# ESP8266.net
KiCad netlist of a schematic drawn in Altium Designer
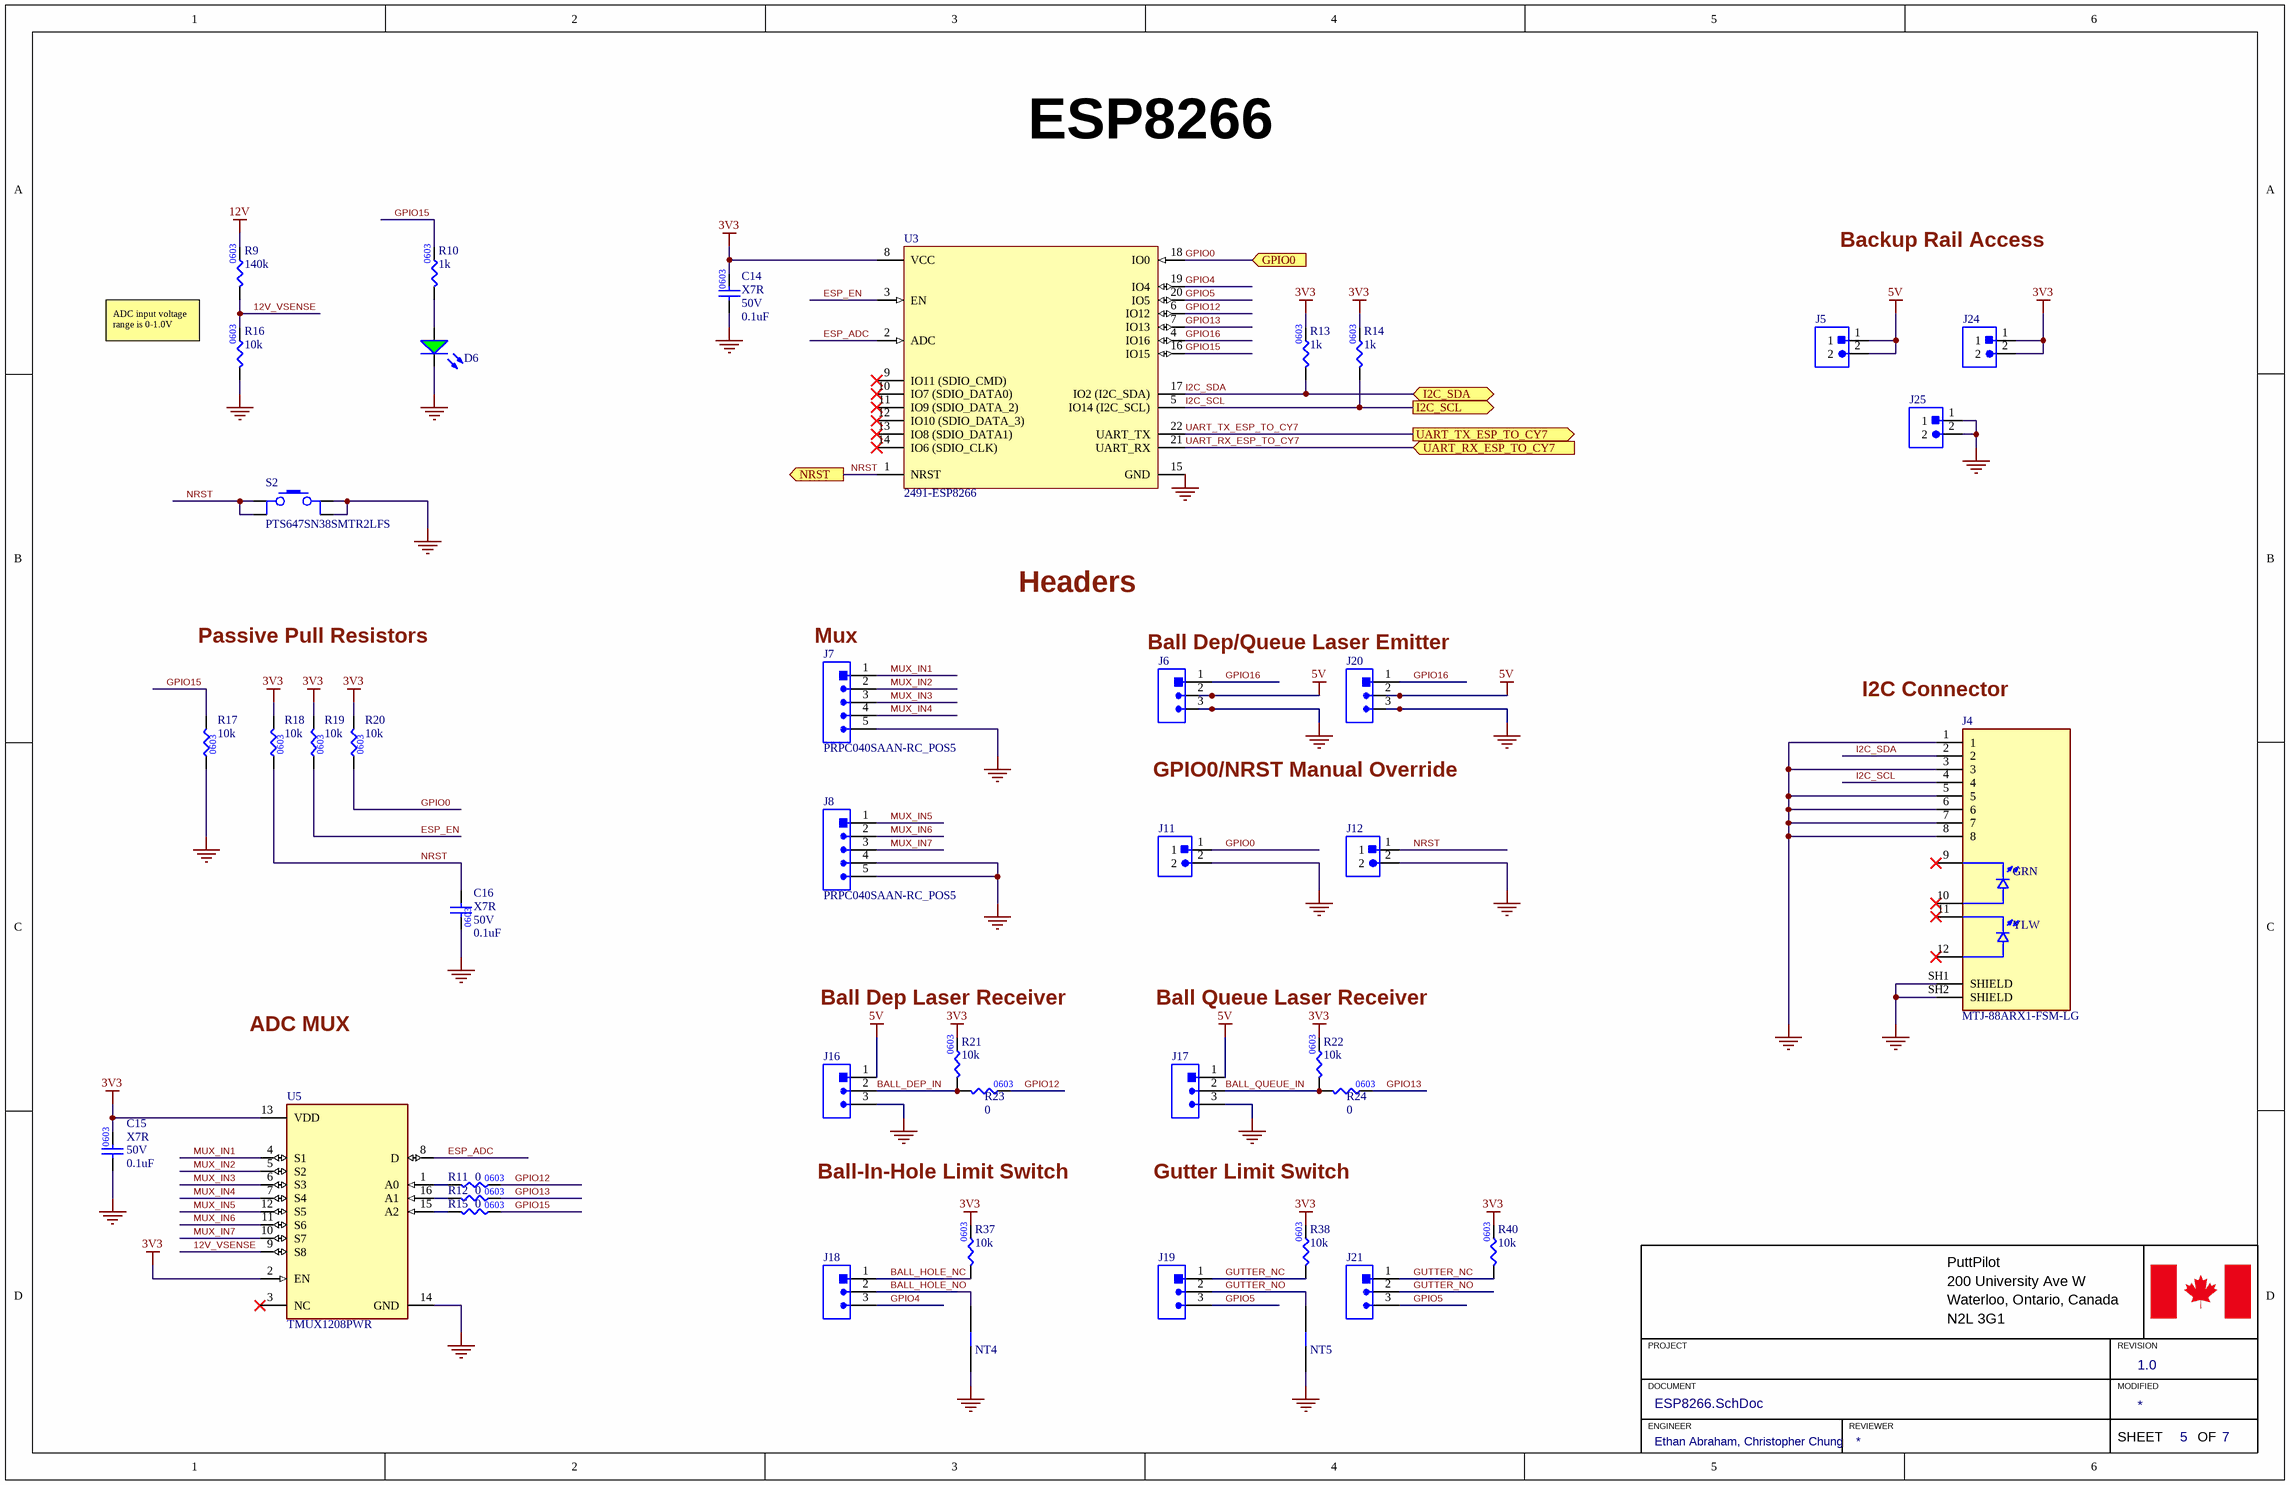
[diagram p0: ESP8266.SchDoc]

(export (version "E")
  (design (tool "Eeschema 10.0.6"))
  (components
    (comp (ref "C14")
      (value "GCJ188R71H104KA12D")
      (footprint ".CAP_0603")
      (description "CAP CER 0.1uF 50V X7R 0603")
      (fields
        (field (name "MANUFACTURER") "Murata")
        (field (name "TEMPERATURE CHARACTERISTICS CODE") "X7R")
        (field (name "RATED DC VOLTAGE (URDC)") "50V")
        (field (name "CAPACITANCE") "0.1uF")
      )
      (libsource (lib "PuttPilot") (part "GCJ188R71H104KA12D"))
    )
    (comp (ref "C15")
      (value "GCJ188R71H104KA12D")
      (footprint ".CAP_0603")
      (description "CAP CER 0.1uF 50V X7R 0603")
      (fields
        (field (name "MANUFACTURER") "Murata")
        (field (name "TEMPERATURE CHARACTERISTICS CODE") "X7R")
        (field (name "RATED DC VOLTAGE (URDC)") "50V")
        (field (name "CAPACITANCE") "0.1uF")
      )
      (libsource (lib "PuttPilot") (part "GCJ188R71H104KA12D"))
    )
    (comp (ref "C16")
      (value "GCJ188R71H104KA12D")
      (footprint ".CAP_0603")
      (description "CAP CER 0.1uF 50V X7R 0603")
      (fields
        (field (name "MANUFACTURER") "Murata")
        (field (name "TEMPERATURE CHARACTERISTICS CODE") "X7R")
        (field (name "RATED DC VOLTAGE (URDC)") "50V")
        (field (name "CAPACITANCE") "0.1uF")
      )
      (libsource (lib "PuttPilot") (part "GCJ188R71H104KA12D"))
    )
    (comp (ref "D6")
      (value "LTST-C191KGKT")
      (footprint ".LED_0603")
      (description "LED GREEN 2V 0603")
      (fields (field (name "MANUFACTURER") "Vishay Lite-On"))
      (libsource (lib "PuttPilot") (part "LTST-C191KGKT"))
    )
    (comp (ref "J4")
      (value "MTJ-88ARX1-FSM-LG")
      (footprint "MTJ-88ARX1-FSM-LG")
      (description "RJ45 JACK R/A SHIELDED")
      (fields (field (name "MANUFACTURER") "Adam Equipment"))
      (libsource (lib "PuttPilot") (part "MTJ-88ARX1-FSM-LG"))
    )
    (comp (ref "J5")
      (value "PRPC040SAAN-RC")
      (footprint "HEADER_2POS_2.54MM")
      (description "CONN HEADER VERT 2POS 2.54MM")
      (fields (field (name "MANUFACTURER") "Sullins"))
      (libsource (lib "PuttPilot") (part "PRPC040SAAN-RC_POS2"))
    )
    (comp (ref "J6")
      (value "PRPC040SAAN-RC")
      (footprint "HEADER_3POS_2.54MM")
      (description "CONN HEADER VERT 3POS 2.54MM")
      (fields (field (name "MANUFACTURER") "Sullins"))
      (libsource (lib "PuttPilot") (part "PRPC040SAAN-RC"))
    )
    (comp (ref "J7")
      (value "PRPC040SAAN-RC_POS5")
      (footprint "HEADER_5POS_2.54MM")
      (description "CONN HEADER VERT 5POS 2.54MM")
      (libsource (lib "PuttPilot") (part "PRPC040SAAN-RC_POS5"))
    )
    (comp (ref "J8")
      (value "PRPC040SAAN-RC_POS5")
      (footprint "HEADER_5POS_2.54MM")
      (description "CONN HEADER VERT 5POS 2.54MM")
      (libsource (lib "PuttPilot") (part "PRPC040SAAN-RC_POS5"))
    )
    (comp (ref "J11")
      (value "PRPC040SAAN-RC")
      (footprint "HEADER_2POS_2.54MM")
      (description "CONN HEADER VERT 2POS 2.54MM")
      (fields (field (name "MANUFACTURER") "Sullins"))
      (libsource (lib "PuttPilot") (part "PRPC040SAAN-RC_POS2"))
    )
    (comp (ref "J12")
      (value "PRPC040SAAN-RC")
      (footprint "HEADER_2POS_2.54MM")
      (description "CONN HEADER VERT 2POS 2.54MM")
      (fields (field (name "MANUFACTURER") "Sullins"))
      (libsource (lib "PuttPilot") (part "PRPC040SAAN-RC_POS2"))
    )
    (comp (ref "J16")
      (value "PRPC040SAAN-RC")
      (footprint "HEADER_3POS_2.54MM")
      (description "CONN HEADER VERT 3POS 2.54MM")
      (fields (field (name "MANUFACTURER") "Sullins"))
      (libsource (lib "PuttPilot") (part "PRPC040SAAN-RC"))
    )
    (comp (ref "J17")
      (value "PRPC040SAAN-RC")
      (footprint "HEADER_3POS_2.54MM")
      (description "CONN HEADER VERT 3POS 2.54MM")
      (fields (field (name "MANUFACTURER") "Sullins"))
      (libsource (lib "PuttPilot") (part "PRPC040SAAN-RC"))
    )
    (comp (ref "J18")
      (value "PRPC040SAAN-RC")
      (footprint "HEADER_3POS_2.54MM")
      (description "CONN HEADER VERT 3POS 2.54MM")
      (fields (field (name "MANUFACTURER") "Sullins"))
      (libsource (lib "PuttPilot") (part "PRPC040SAAN-RC"))
    )
    (comp (ref "J19")
      (value "PRPC040SAAN-RC")
      (footprint "HEADER_3POS_2.54MM")
      (description "CONN HEADER VERT 3POS 2.54MM")
      (fields (field (name "MANUFACTURER") "Sullins"))
      (libsource (lib "PuttPilot") (part "PRPC040SAAN-RC"))
    )
    (comp (ref "J20")
      (value "PRPC040SAAN-RC")
      (footprint "HEADER_3POS_2.54MM")
      (description "CONN HEADER VERT 3POS 2.54MM")
      (fields (field (name "MANUFACTURER") "Sullins"))
      (libsource (lib "PuttPilot") (part "PRPC040SAAN-RC"))
    )
    (comp (ref "J21")
      (value "PRPC040SAAN-RC")
      (footprint "HEADER_3POS_2.54MM")
      (description "CONN HEADER VERT 3POS 2.54MM")
      (fields (field (name "MANUFACTURER") "Sullins"))
      (libsource (lib "PuttPilot") (part "PRPC040SAAN-RC"))
    )
    (comp (ref "J24")
      (value "PRPC040SAAN-RC")
      (footprint "HEADER_2POS_2.54MM")
      (description "CONN HEADER VERT 2POS 2.54MM")
      (fields (field (name "MANUFACTURER") "Sullins"))
      (libsource (lib "PuttPilot") (part "PRPC040SAAN-RC_POS2"))
    )
    (comp (ref "J25")
      (value "PRPC040SAAN-RC")
      (footprint "HEADER_2POS_2.54MM")
      (description "CONN HEADER VERT 2POS 2.54MM")
      (fields (field (name "MANUFACTURER") "Sullins"))
      (libsource (lib "PuttPilot") (part "PRPC040SAAN-RC_POS2"))
    )
    (comp (ref "NT4")
      (value ".NET_TIE")
      (footprint ".NET_TIE")
      (description ".GENERIC NET TIE")
      (libsource (lib "PuttPilot") (part ".NET_TIE"))
    )
    (comp (ref "NT5")
      (value ".NET_TIE")
      (footprint ".NET_TIE")
      (description ".GENERIC NET TIE")
      (libsource (lib "PuttPilot") (part ".NET_TIE"))
    )
    (comp (ref "R9")
      (value "RC0603FR-07140KL")
      (footprint ".RES_0603")
      (description "RES 140K OHM 0603")
      (fields
        (field (name "MANUFACTURER") "Yageo")
        (field (name "TOLERANCE") "1%")
        (field (name "RESISTANCE") "140k")
      )
      (libsource (lib "PuttPilot") (part "RC0603FR-07140KL"))
    )
    (comp (ref "R10")
      (value "RC0603FR-071KL")
      (footprint ".RES_0603")
      (description "RES 1K OHM 0603")
      (fields
        (field (name "MANUFACTURER") "Yageo")
        (field (name "TOLERANCE") "1%")
        (field (name "RESISTANCE") "1k")
      )
      (libsource (lib "PuttPilot") (part "RC0603FR-071KL"))
    )
    (comp (ref "R11")
      (value "RC0603JR-070RL")
      (footprint ".RES_0603")
      (description "RES 0 OHM 0603")
      (fields
        (field (name "MANUFACTURER") "Yageo")
        (field (name "MANUFACTURER PART NUMBER") "RC0603FR-071KL")
        (field (name "RESISTANCE") "0")
      )
      (libsource (lib "PuttPilot") (part "RC0603JR-070RL"))
    )
    (comp (ref "R12")
      (value "RC0603JR-070RL")
      (footprint ".RES_0603")
      (description "RES 0 OHM 0603")
      (fields
        (field (name "MANUFACTURER") "Yageo")
        (field (name "MANUFACTURER PART NUMBER") "RC0603FR-071KL")
        (field (name "RESISTANCE") "0")
      )
      (libsource (lib "PuttPilot") (part "RC0603JR-070RL"))
    )
    (comp (ref "R13")
      (value "RC0603FR-071KL")
      (footprint ".RES_0603")
      (description "RES 1K OHM 0603")
      (fields
        (field (name "MANUFACTURER") "Yageo")
        (field (name "TOLERANCE") "1%")
        (field (name "RESISTANCE") "1k")
      )
      (libsource (lib "PuttPilot") (part "RC0603FR-071KL"))
    )
    (comp (ref "R14")
      (value "RC0603FR-071KL")
      (footprint ".RES_0603")
      (description "RES 1K OHM 0603")
      (fields
        (field (name "MANUFACTURER") "Yageo")
        (field (name "TOLERANCE") "1%")
        (field (name "RESISTANCE") "1k")
      )
      (libsource (lib "PuttPilot") (part "RC0603FR-071KL"))
    )
    (comp (ref "R15")
      (value "RC0603JR-070RL")
      (footprint ".RES_0603")
      (description "RES 0 OHM 0603")
      (fields
        (field (name "MANUFACTURER") "Yageo")
        (field (name "MANUFACTURER PART NUMBER") "RC0603FR-071KL")
        (field (name "RESISTANCE") "0")
      )
      (libsource (lib "PuttPilot") (part "RC0603JR-070RL"))
    )
    (comp (ref "R16")
      (value "RC0603FR-0710KL")
      (footprint ".RES_0603")
      (description "RES 10K OHM 0603")
      (fields
        (field (name "MANUFACTURER") "Yageo")
        (field (name "TOLERANCE") "1%")
        (field (name "RESISTANCE") "10k")
      )
      (libsource (lib "PuttPilot") (part "RC0603FR-0710KL"))
    )
    (comp (ref "R17")
      (value "RC0603FR-0710KL")
      (footprint ".RES_0603")
      (description "RES 10K OHM 0603")
      (fields
        (field (name "MANUFACTURER") "Yageo")
        (field (name "TOLERANCE") "1%")
        (field (name "RESISTANCE") "10k")
      )
      (libsource (lib "PuttPilot") (part "RC0603FR-0710KL"))
    )
    (comp (ref "R18")
      (value "RC0603FR-0710KL")
      (footprint ".RES_0603")
      (description "RES 10K OHM 0603")
      (fields
        (field (name "MANUFACTURER") "Yageo")
        (field (name "TOLERANCE") "1%")
        (field (name "RESISTANCE") "10k")
      )
      (libsource (lib "PuttPilot") (part "RC0603FR-0710KL"))
    )
    (comp (ref "R19")
      (value "RC0603FR-0710KL")
      (footprint ".RES_0603")
      (description "RES 10K OHM 0603")
      (fields
        (field (name "MANUFACTURER") "Yageo")
        (field (name "TOLERANCE") "1%")
        (field (name "RESISTANCE") "10k")
      )
      (libsource (lib "PuttPilot") (part "RC0603FR-0710KL"))
    )
    (comp (ref "R20")
      (value "RC0603FR-0710KL")
      (footprint ".RES_0603")
      (description "RES 10K OHM 0603")
      (fields
        (field (name "MANUFACTURER") "Yageo")
        (field (name "TOLERANCE") "1%")
        (field (name "RESISTANCE") "10k")
      )
      (libsource (lib "PuttPilot") (part "RC0603FR-0710KL"))
    )
    (comp (ref "R21")
      (value "RC0603FR-0710KL")
      (footprint ".RES_0603")
      (description "RES 10K OHM 0603")
      (fields
        (field (name "MANUFACTURER") "Yageo")
        (field (name "TOLERANCE") "1%")
        (field (name "RESISTANCE") "10k")
      )
      (libsource (lib "PuttPilot") (part "RC0603FR-0710KL"))
    )
    (comp (ref "R22")
      (value "RC0603FR-0710KL")
      (footprint ".RES_0603")
      (description "RES 10K OHM 0603")
      (fields
        (field (name "MANUFACTURER") "Yageo")
        (field (name "TOLERANCE") "1%")
        (field (name "RESISTANCE") "10k")
      )
      (libsource (lib "PuttPilot") (part "RC0603FR-0710KL"))
    )
    (comp (ref "R23")
      (value "RC0603JR-070RL")
      (footprint ".RES_0603")
      (description "RES 0 OHM 0603")
      (fields
        (field (name "MANUFACTURER") "Yageo")
        (field (name "MANUFACTURER PART NUMBER") "RC0603FR-071KL")
        (field (name "RESISTANCE") "0")
      )
      (libsource (lib "PuttPilot") (part "RC0603JR-070RL"))
    )
    (comp (ref "R24")
      (value "RC0603JR-070RL")
      (footprint ".RES_0603")
      (description "RES 0 OHM 0603")
      (fields
        (field (name "MANUFACTURER") "Yageo")
        (field (name "MANUFACTURER PART NUMBER") "RC0603FR-071KL")
        (field (name "RESISTANCE") "0")
      )
      (libsource (lib "PuttPilot") (part "RC0603JR-070RL"))
    )
    (comp (ref "R37")
      (value "RC0603FR-0710KL")
      (footprint ".RES_0603")
      (description "RES 10K OHM 0603")
      (fields
        (field (name "MANUFACTURER") "Yageo")
        (field (name "TOLERANCE") "1%")
        (field (name "RESISTANCE") "10k")
      )
      (libsource (lib "PuttPilot") (part "RC0603FR-0710KL"))
    )
    (comp (ref "R38")
      (value "RC0603FR-0710KL")
      (footprint ".RES_0603")
      (description "RES 10K OHM 0603")
      (fields
        (field (name "MANUFACTURER") "Yageo")
        (field (name "TOLERANCE") "1%")
        (field (name "RESISTANCE") "10k")
      )
      (libsource (lib "PuttPilot") (part "RC0603FR-0710KL"))
    )
    (comp (ref "R40")
      (value "RC0603FR-0710KL")
      (footprint ".RES_0603")
      (description "RES 10K OHM 0603")
      (fields
        (field (name "MANUFACTURER") "Yageo")
        (field (name "TOLERANCE") "1%")
        (field (name "RESISTANCE") "10k")
      )
      (libsource (lib "PuttPilot") (part "RC0603FR-0710KL"))
    )
    (comp (ref "S2")
      (value "PTS647SN38SMTR2LFS")
      (footprint "PTS647SN38SMTR2LFS")
      (description "SWITCH TACTILE SPST-NO 0.05A 12V")
      (fields (field (name "MANUFACTURER") "ITT C&K"))
      (libsource (lib "PuttPilot") (part "PTS647SN38SMTR2LFS"))
    )
    (comp (ref "U3")
      (value "2491-ESP8266")
      (footprint "2491-ESP8266")
      (description "ESP8266 + Trace Antenna, 4MB Flash")
      (libsource (lib "PuttPilot") (part "2491-ESP8266"))
    )
    (comp (ref "U5")
      (value "TMUX1208PWR")
      (footprint "TMUX1208")
      (description "Single-Ended Multiplexer, 1 Func, 8 Channel, CMOS, PDSO16")
      (fields (field (name "MANUFACTURER") "Texas Instruments"))
      (libsource (lib "PuttPilot") (part "TMUX1208PWR"))
    )
  )
  (nets
    (net (code "1") (name "/12V_VSENSE") (class "Default")
      (node (ref "R16") (pin "2") (pinfunction "2_2") (pintype "passive"))
      (node (ref "R9") (pin "1") (pinfunction "1_1") (pintype "passive"))
      (node (ref "U5") (pin "9") (pinfunction "S8_9") (pintype "bidirectional"))
    )
    (net (code "2") (name "/BALL_DEP_IN") (class "Default")
      (node (ref "J16") (pin "2") (pinfunction "2_2") (pintype "passive"))
      (node (ref "R21") (pin "1") (pinfunction "1_1") (pintype "passive"))
      (node (ref "R23") (pin "1") (pinfunction "1_1") (pintype "passive"))
    )
    (net (code "3") (name "/BALL_HOLE_NC") (class "Default")
      (node (ref "J18") (pin "1") (pinfunction "1_1") (pintype "passive"))
      (node (ref "R37") (pin "1") (pinfunction "1_1") (pintype "passive"))
    )
    (net (code "4") (name "/BALL_HOLE_NO") (class "Default")
      (node (ref "J18") (pin "2") (pinfunction "2_2") (pintype "passive"))
      (node (ref "NT4") (pin "2") (pinfunction "2_2") (pintype "passive"))
    )
    (net (code "5") (name "/BALL_QUEUE_IN") (class "Default")
      (node (ref "J17") (pin "2") (pinfunction "2_2") (pintype "passive"))
      (node (ref "R22") (pin "1") (pinfunction "1_1") (pintype "passive"))
      (node (ref "R24") (pin "1") (pinfunction "1_1") (pintype "passive"))
    )
    (net (code "6") (name "/ESP_ADC") (class "Default")
      (node (ref "U3") (pin "2") (pinfunction "ADC_2") (pintype "input"))
      (node (ref "U5") (pin "8") (pinfunction "D_8") (pintype "bidirectional"))
    )
    (net (code "7") (name "/ESP_EN") (class "Default")
      (node (ref "R19") (pin "1") (pinfunction "1_1") (pintype "passive"))
      (node (ref "U3") (pin "3") (pinfunction "EN_3") (pintype "input"))
    )
    (net (code "8") (name "/GPIO0") (class "Default")
      (node (ref "J11") (pin "1") (pinfunction "1_1") (pintype "passive"))
      (node (ref "R20") (pin "1") (pinfunction "1_1") (pintype "passive"))
      (node (ref "U3") (pin "18") (pinfunction "IO0_18") (pintype "input"))
    )
    (net (code "9") (name "/GPIO4") (class "Default")
      (node (ref "J18") (pin "3") (pinfunction "3_3") (pintype "passive"))
      (node (ref "U3") (pin "19") (pinfunction "IO4_19") (pintype "bidirectional"))
    )
    (net (code "10") (name "/GPIO5") (class "Default")
      (node (ref "J19") (pin "3") (pinfunction "3_3") (pintype "passive"))
      (node (ref "J21") (pin "3") (pinfunction "3_3") (pintype "passive"))
      (node (ref "U3") (pin "20") (pinfunction "IO5_20") (pintype "bidirectional"))
    )
    (net (code "11") (name "/GPIO12") (class "Default")
      (node (ref "R11") (pin "2") (pinfunction "2_2") (pintype "passive"))
      (node (ref "R23") (pin "2") (pinfunction "2_2") (pintype "passive"))
      (node (ref "U3") (pin "6") (pinfunction "IO12_6") (pintype "bidirectional"))
    )
    (net (code "12") (name "/GPIO13") (class "Default")
      (node (ref "R12") (pin "2") (pinfunction "2_2") (pintype "passive"))
      (node (ref "R24") (pin "2") (pinfunction "2_2") (pintype "passive"))
      (node (ref "U3") (pin "7") (pinfunction "IO13_7") (pintype "bidirectional"))
    )
    (net (code "13") (name "/GPIO15") (class "Default")
      (node (ref "R10") (pin "2") (pinfunction "2_2") (pintype "passive"))
      (node (ref "R15") (pin "2") (pinfunction "2_2") (pintype "passive"))
      (node (ref "R17") (pin "2") (pinfunction "2_2") (pintype "passive"))
      (node (ref "U3") (pin "16") (pinfunction "IO15_16") (pintype "bidirectional"))
    )
    (net (code "14") (name "/GPIO16") (class "Default")
      (node (ref "J20") (pin "1") (pinfunction "1_1") (pintype "passive"))
      (node (ref "J6") (pin "1") (pinfunction "1_1") (pintype "passive"))
      (node (ref "U3") (pin "4") (pinfunction "IO16_4") (pintype "bidirectional"))
    )
    (net (code "15") (name "/GUTTER_NC") (class "Default")
      (node (ref "J19") (pin "1") (pinfunction "1_1") (pintype "passive"))
      (node (ref "J21") (pin "1") (pinfunction "1_1") (pintype "passive"))
      (node (ref "R38") (pin "1") (pinfunction "1_1") (pintype "passive"))
      (node (ref "R40") (pin "1") (pinfunction "1_1") (pintype "passive"))
    )
    (net (code "16") (name "/GUTTER_NO") (class "Default")
      (node (ref "J19") (pin "2") (pinfunction "2_2") (pintype "passive"))
      (node (ref "J21") (pin "2") (pinfunction "2_2") (pintype "passive"))
      (node (ref "NT5") (pin "2") (pinfunction "2_2") (pintype "passive"))
    )
    (net (code "17") (name "/I2C_SCL") (class "Default")
      (node (ref "J4") (pin "4") (pinfunction "4_4") (pintype "passive"))
      (node (ref "R14") (pin "1") (pinfunction "1_1") (pintype "passive"))
      (node (ref "U3") (pin "5") (pinfunction "IO14_(I2C_SCL)_5") (pintype "passive"))
    )
    (net (code "18") (name "/I2C_SDA") (class "Default")
      (node (ref "J4") (pin "2") (pinfunction "2_2") (pintype "passive"))
      (node (ref "R13") (pin "1") (pinfunction "1_1") (pintype "passive"))
      (node (ref "U3") (pin "17") (pinfunction "IO2_(I2C_SDA)_17") (pintype "passive"))
    )
    (net (code "19") (name "/MUX_IN1") (class "Default")
      (node (ref "J7") (pin "1") (pinfunction "1_1") (pintype "passive"))
      (node (ref "U5") (pin "4") (pinfunction "S1_4") (pintype "bidirectional"))
    )
    (net (code "20") (name "/MUX_IN2") (class "Default")
      (node (ref "J7") (pin "2") (pinfunction "2_2") (pintype "passive"))
      (node (ref "U5") (pin "5") (pinfunction "S2_5") (pintype "bidirectional"))
    )
    (net (code "21") (name "/MUX_IN3") (class "Default")
      (node (ref "J7") (pin "3") (pinfunction "3_3") (pintype "passive"))
      (node (ref "U5") (pin "6") (pinfunction "S3_6") (pintype "bidirectional"))
    )
    (net (code "22") (name "/MUX_IN4") (class "Default")
      (node (ref "J7") (pin "4") (pinfunction "4_4") (pintype "passive"))
      (node (ref "U5") (pin "7") (pinfunction "S4_7") (pintype "bidirectional"))
    )
    (net (code "23") (name "/MUX_IN5") (class "Default")
      (node (ref "J8") (pin "1") (pinfunction "1_1") (pintype "passive"))
      (node (ref "U5") (pin "12") (pinfunction "S5_12") (pintype "bidirectional"))
    )
    (net (code "24") (name "/MUX_IN6") (class "Default")
      (node (ref "J8") (pin "2") (pinfunction "2_2") (pintype "passive"))
      (node (ref "U5") (pin "11") (pinfunction "S6_11") (pintype "bidirectional"))
    )
    (net (code "25") (name "/MUX_IN7") (class "Default")
      (node (ref "J8") (pin "3") (pinfunction "3_3") (pintype "passive"))
      (node (ref "U5") (pin "10") (pinfunction "S7_10") (pintype "bidirectional"))
    )
    (net (code "26") (name "/NRST") (class "Default")
      (node (ref "C16") (pin "2") (pinfunction "2_2") (pintype "passive"))
      (node (ref "J12") (pin "1") (pinfunction "1_1") (pintype "passive"))
      (node (ref "R18") (pin "1") (pinfunction "1_1") (pintype "passive"))
      (node (ref "S2") (pin "1") (pinfunction "1_1") (pintype "passive"))
      (node (ref "S2") (pin "2") (pinfunction "2_2") (pintype "passive"))
      (node (ref "U3") (pin "1") (pinfunction "NRST_1") (pintype "passive"))
    )
    (net (code "27") (name "/UART_RX_ESP_TO_CY7") (class "Default")
      (node (ref "U3") (pin "21") (pinfunction "UART_RX_21") (pintype "passive"))
    )
    (net (code "28") (name "/UART_TX_ESP_TO_CY7") (class "Default")
      (node (ref "U3") (pin "22") (pinfunction "UART_TX_22") (pintype "passive"))
    )
    (net (code "29") (name "3V3") (class "Default")
      (node (ref "C14") (pin "2") (pinfunction "2_2") (pintype "passive"))
      (node (ref "C15") (pin "2") (pinfunction "2_2") (pintype "passive"))
      (node (ref "J24") (pin "1") (pinfunction "1_1") (pintype "passive"))
      (node (ref "J24") (pin "2") (pinfunction "2_2") (pintype "passive"))
      (node (ref "R13") (pin "2") (pinfunction "2_2") (pintype "passive"))
      (node (ref "R14") (pin "2") (pinfunction "2_2") (pintype "passive"))
      (node (ref "R18") (pin "2") (pinfunction "2_2") (pintype "passive"))
      (node (ref "R19") (pin "2") (pinfunction "2_2") (pintype "passive"))
      (node (ref "R20") (pin "2") (pinfunction "2_2") (pintype "passive"))
      (node (ref "R21") (pin "2") (pinfunction "2_2") (pintype "passive"))
      (node (ref "R22") (pin "2") (pinfunction "2_2") (pintype "passive"))
      (node (ref "R37") (pin "2") (pinfunction "2_2") (pintype "passive"))
      (node (ref "R38") (pin "2") (pinfunction "2_2") (pintype "passive"))
      (node (ref "R40") (pin "2") (pinfunction "2_2") (pintype "passive"))
      (node (ref "U3") (pin "8") (pinfunction "VCC_8") (pintype "power_in"))
      (node (ref "U5") (pin "13") (pinfunction "VDD_13") (pintype "power_in"))
      (node (ref "U5") (pin "2") (pinfunction "EN_2") (pintype "input"))
    )
    (net (code "30") (name "5V") (class "Default")
      (node (ref "J16") (pin "1") (pinfunction "1_1") (pintype "passive"))
      (node (ref "J17") (pin "1") (pinfunction "1_1") (pintype "passive"))
      (node (ref "J20") (pin "2") (pinfunction "2_2") (pintype "passive"))
      (node (ref "J5") (pin "1") (pinfunction "1_1") (pintype "passive"))
      (node (ref "J5") (pin "2") (pinfunction "2_2") (pintype "passive"))
      (node (ref "J6") (pin "2") (pinfunction "2_2") (pintype "passive"))
    )
    (net (code "31") (name "12V") (class "Default")
      (node (ref "R9") (pin "2") (pinfunction "2_2") (pintype "passive"))
    )
    (net (code "32") (name "GND") (class "Default")
      (node (ref "C14") (pin "1") (pinfunction "1_1") (pintype "passive"))
      (node (ref "C15") (pin "1") (pinfunction "1_1") (pintype "passive"))
      (node (ref "C16") (pin "1") (pinfunction "1_1") (pintype "passive"))
      (node (ref "D6") (pin "2") (pinfunction "K_2") (pintype "passive"))
      (node (ref "J11") (pin "2") (pinfunction "2_2") (pintype "passive"))
      (node (ref "J12") (pin "2") (pinfunction "2_2") (pintype "passive"))
      (node (ref "J16") (pin "3") (pinfunction "3_3") (pintype "passive"))
      (node (ref "J17") (pin "3") (pinfunction "3_3") (pintype "passive"))
      (node (ref "J20") (pin "3") (pinfunction "3_3") (pintype "passive"))
      (node (ref "J25") (pin "1") (pinfunction "1_1") (pintype "passive"))
      (node (ref "J25") (pin "2") (pinfunction "2_2") (pintype "passive"))
      (node (ref "J4") (pin "1") (pinfunction "1_1") (pintype "passive"))
      (node (ref "J4") (pin "3") (pinfunction "3_3") (pintype "passive"))
      (node (ref "J4") (pin "5") (pinfunction "5_5") (pintype "passive"))
      (node (ref "J4") (pin "6") (pinfunction "6_6") (pintype "passive"))
      (node (ref "J4") (pin "7") (pinfunction "7_7") (pintype "passive"))
      (node (ref "J4") (pin "8") (pinfunction "8_8") (pintype "passive"))
      (node (ref "J4") (pin "SH1") (pinfunction "SHIELD_SH1") (pintype "passive"))
      (node (ref "J4") (pin "SH2") (pinfunction "SHIELD_SH2") (pintype "passive"))
      (node (ref "J6") (pin "3") (pinfunction "3_3") (pintype "passive"))
      (node (ref "J7") (pin "5") (pinfunction "5_5") (pintype "passive"))
      (node (ref "J8") (pin "4") (pinfunction "4_4") (pintype "passive"))
      (node (ref "J8") (pin "5") (pinfunction "5_5") (pintype "passive"))
      (node (ref "NT4") (pin "1") (pinfunction "1_1") (pintype "passive"))
      (node (ref "NT5") (pin "1") (pinfunction "1_1") (pintype "passive"))
      (node (ref "R16") (pin "1") (pinfunction "1_1") (pintype "passive"))
      (node (ref "R17") (pin "1") (pinfunction "1_1") (pintype "passive"))
      (node (ref "S2") (pin "3") (pinfunction "3_3") (pintype "passive"))
      (node (ref "S2") (pin "4") (pinfunction "4_4") (pintype "passive"))
      (node (ref "U3") (pin "15") (pinfunction "GND_15") (pintype "power_in"))
      (node (ref "U5") (pin "14") (pinfunction "GND_14") (pintype "power_in"))
    )
    (net (code "33") (name "Net-(D6-A)") (class "Default")
      (node (ref "D6") (pin "1") (pinfunction "A_1") (pintype "passive"))
      (node (ref "R10") (pin "1") (pinfunction "1_1") (pintype "passive"))
    )
    (net (code "34") (name "Net-(U5-A0)") (class "Default")
      (node (ref "R11") (pin "1") (pinfunction "1_1") (pintype "passive"))
      (node (ref "U5") (pin "1") (pinfunction "A0_1") (pintype "input"))
    )
    (net (code "35") (name "Net-(U5-A1)") (class "Default")
      (node (ref "R12") (pin "1") (pinfunction "1_1") (pintype "passive"))
      (node (ref "U5") (pin "16") (pinfunction "A1_16") (pintype "input"))
    )
    (net (code "36") (name "Net-(U5-A2)") (class "Default")
      (node (ref "R15") (pin "1") (pinfunction "1_1") (pintype "passive"))
      (node (ref "U5") (pin "15") (pinfunction "A2_15") (pintype "input"))
    )
    (net (code "37") (name "unconnected-(J4-Pad9)") (class "Default")
      (node (ref "J4") (pin "9") (pinfunction "9_9") (pintype "passive+no_connect"))
    )
    (net (code "38") (name "unconnected-(J4-Pad10)") (class "Default")
      (node (ref "J4") (pin "10") (pinfunction "10_10") (pintype "passive+no_connect"))
    )
    (net (code "39") (name "unconnected-(J4-Pad11)") (class "Default")
      (node (ref "J4") (pin "11") (pinfunction "11_11") (pintype "passive+no_connect"))
    )
    (net (code "40") (name "unconnected-(J4-Pad12)") (class "Default")
      (node (ref "J4") (pin "12") (pinfunction "12_12") (pintype "passive+no_connect"))
    )
    (net (code "41") (name "unconnected-(U3-IO6_(SDIO_CLK)-Pad14)") (class "Default")
      (node (ref "U3") (pin "14") (pinfunction "IO6_(SDIO_CLK)_14") (pintype "passive+no_connect"))
    )
    (net (code "42") (name "unconnected-(U3-IO7_(SDIO_DATA0)-Pad10)") (class "Default")
      (node (ref "U3") (pin "10") (pinfunction "IO7_(SDIO_DATA0)_10") (pintype "passive+no_connect"))
    )
    (net (code "43") (name "unconnected-(U3-IO8_(SDIO_DATA1)-Pad13)") (class "Default")
      (node (ref "U3") (pin "13") (pinfunction "IO8_(SDIO_DATA1)_13") (pintype "passive+no_connect"))
    )
    (net (code "44") (name "unconnected-(U3-IO9_(SDIO_DATA_2)-Pad11)") (class "Default")
      (node (ref "U3") (pin "11") (pinfunction "IO9_(SDIO_DATA_2)_11") (pintype "passive+no_connect"))
    )
    (net (code "45") (name "unconnected-(U3-IO10_(SDIO_DATA_3)-Pad12)") (class "Default")
      (node (ref "U3") (pin "12") (pinfunction "IO10_(SDIO_DATA_3)_12") (pintype "passive+no_connect"))
    )
    (net (code "46") (name "unconnected-(U3-IO11_(SDIO_CMD)-Pad9)") (class "Default")
      (node (ref "U3") (pin "9") (pinfunction "IO11_(SDIO_CMD)_9") (pintype "passive+no_connect"))
    )
    (net (code "47") (name "unconnected-(U5-NC-Pad3)") (class "Default")
      (node (ref "U5") (pin "3") (pinfunction "NC_3") (pintype "passive+no_connect"))
    )
  )
)
